# PMD_PROJECT.net
KiCad netlist of a schematic drawn in EasyEDA
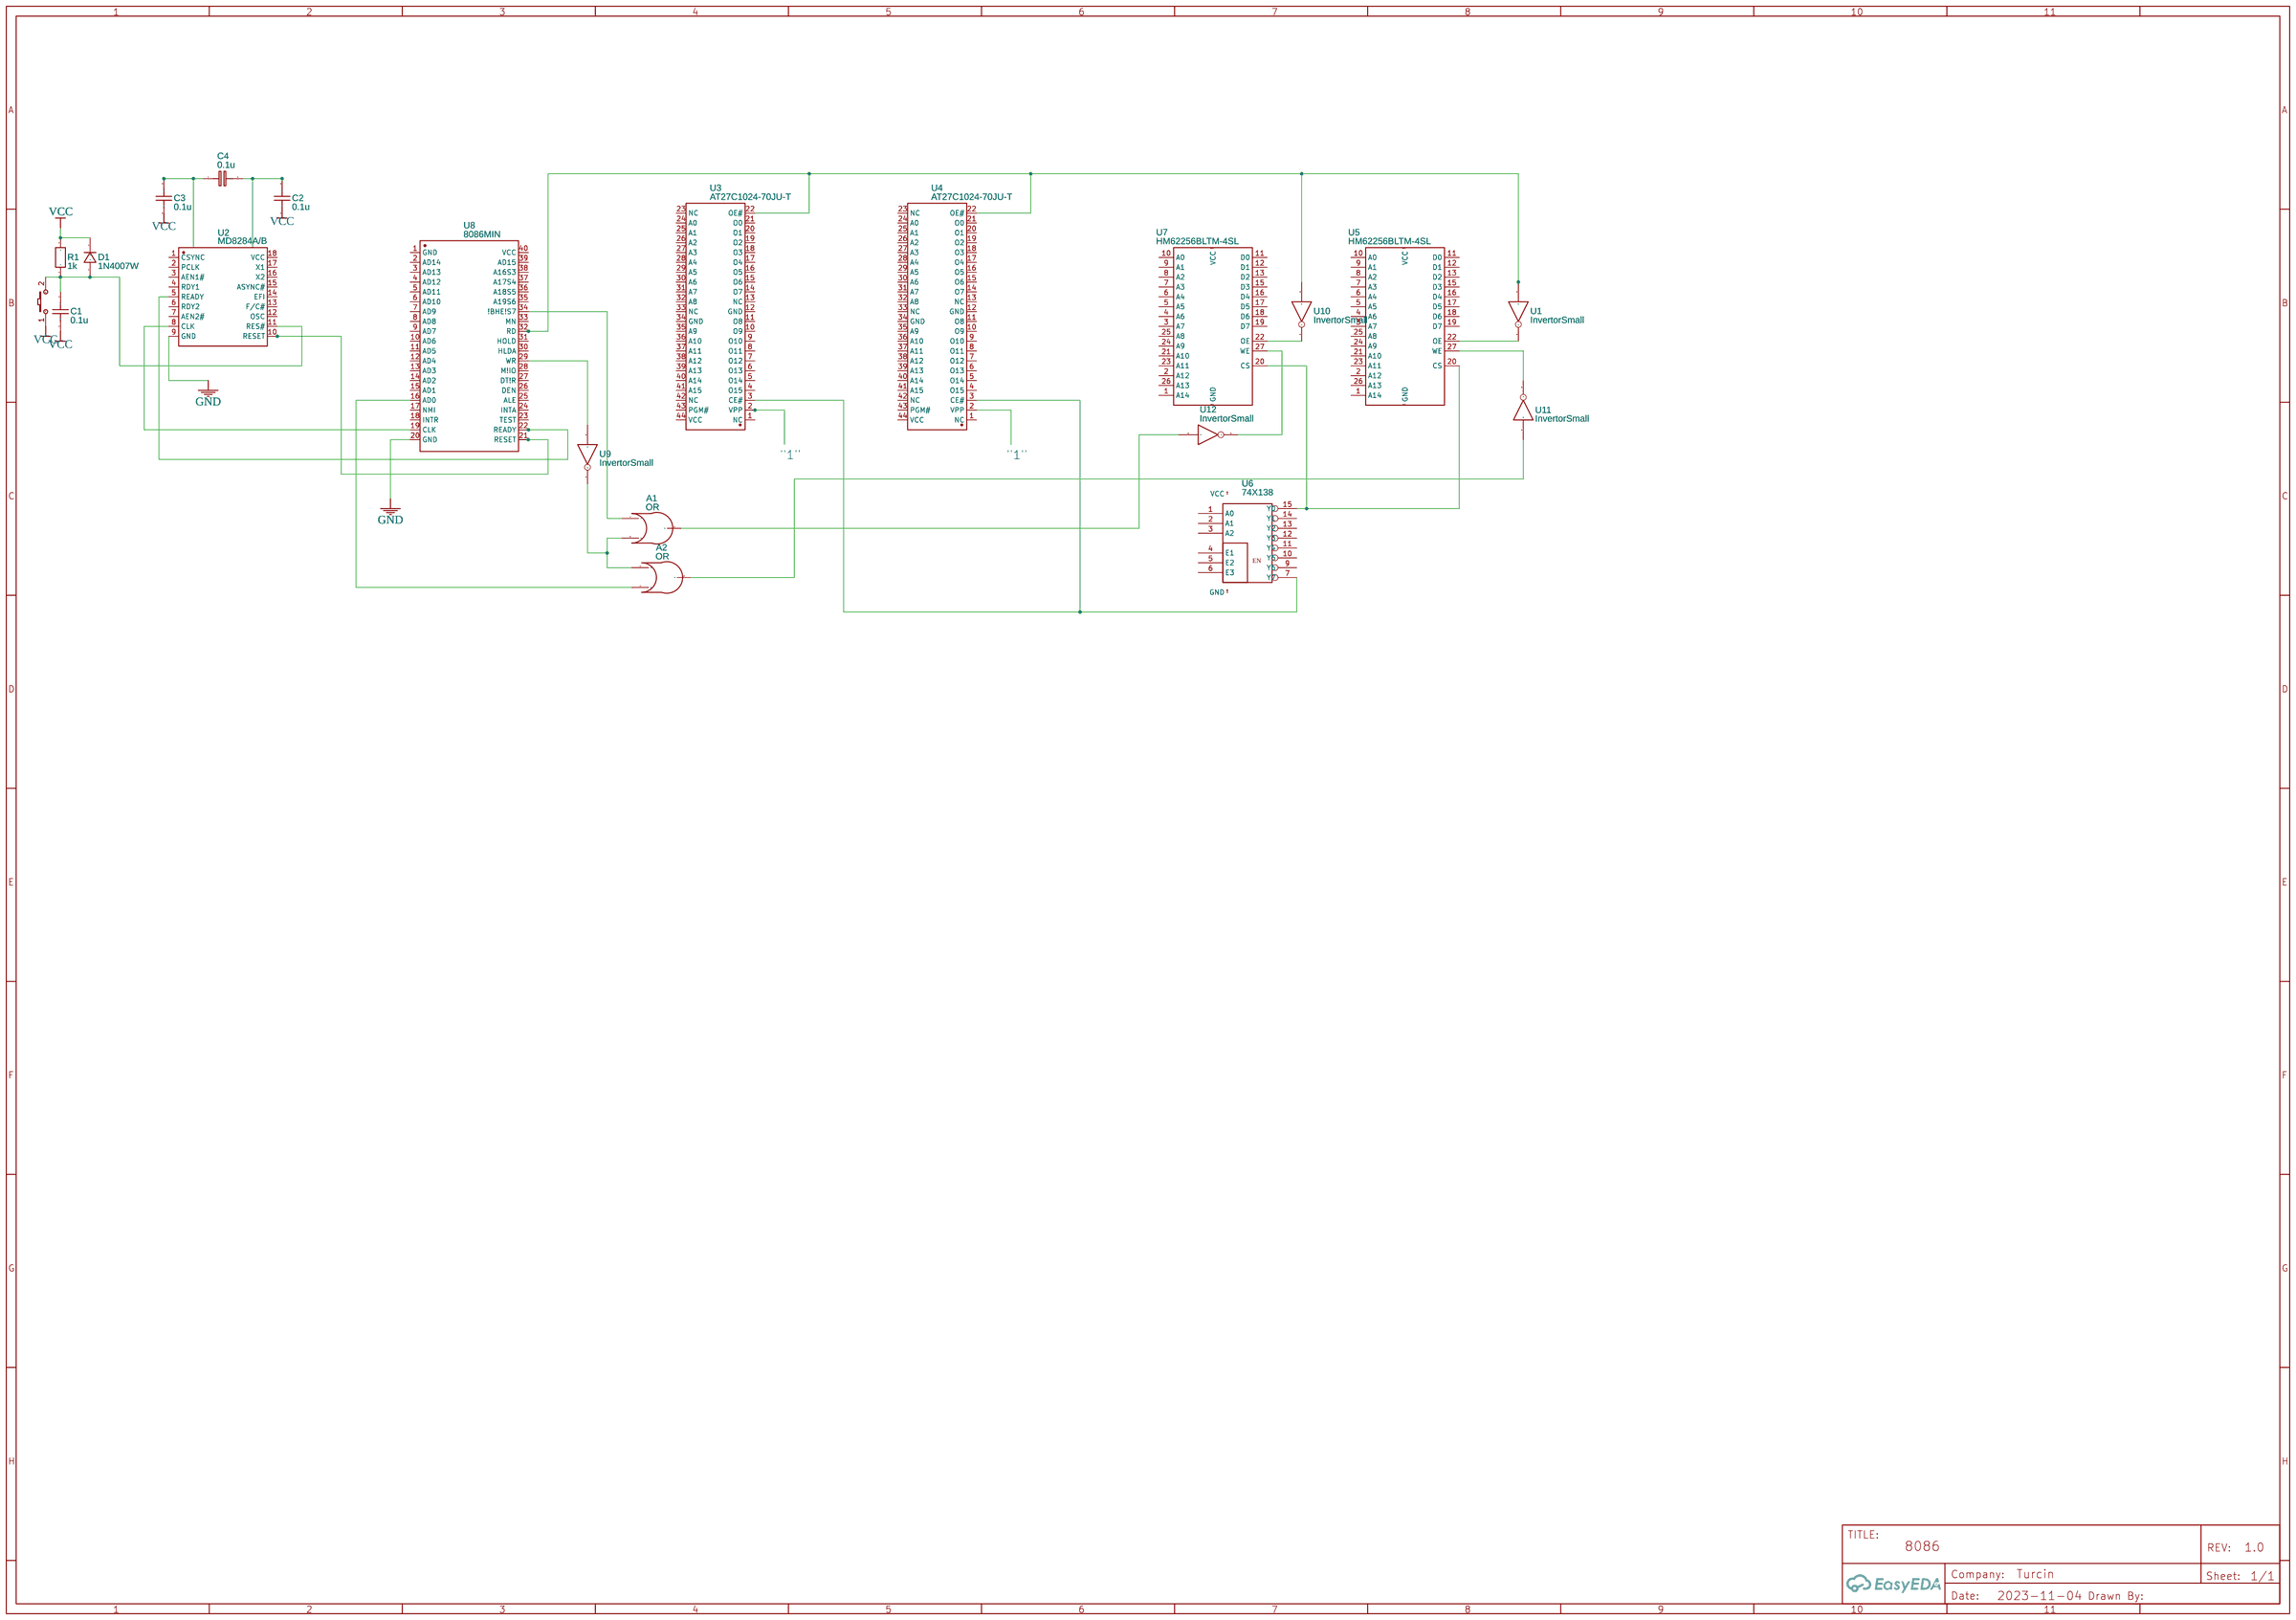
[diagram p0: schematic sheet]

(export (version "E")
  (design (tool "Eeschema 10.0.6"))
  (components
    (comp (ref "A1") (value "OR") (libsource (lib "") (part "OR")))
    (comp (ref "A2") (value "OR") (libsource (lib "") (part "OR")))
    (comp (ref "C1") (value "0.1u") (libsource (lib "") (part "C_0603_US")))
    (comp (ref "C2") (value "0.1u") (libsource (lib "") (part "C_0603_US")))
    (comp (ref "C3") (value "0.1u") (libsource (lib "") (part "C_0603_US")))
    (comp (ref "C4") (value "0.1u") (libsource (lib "") (part "C_0603_EU")))
    (comp (ref "D1")
      (value "1N4007W")
      (fields (field (name "Manufacturer") "BLUE ROCKET"))
      (libsource (lib "") (part "1N4007W"))
    )
    (comp (ref "KEY1")
      (value "K2-3.6×6.1_SMD")
      (fields (field (name "Manufacturer Part") "K2-1107ST-A4SW-06"))
      (libsource (lib "") (part "K2-3.6×6.1_SMD"))
    )
    (comp (ref "R1") (value "1k") (libsource (lib "") (part "R_0603_EU")))
    (comp (ref "U1") (value "InvertorSmall") (libsource (lib "") (part "LOGIC_1")))
    (comp (ref "U2")
      (value "MD8284A/B")
      (fields (field (name "Manufacturer") "罗彻斯特"))
      (libsource (lib "") (part "MD8284A/B"))
    )
    (comp (ref "U3")
      (value "AT27C1024-70JU-T")
      (fields (field (name "Manufacturer") "MICROCHIP(美国微芯)"))
      (libsource (lib "") (part "AT27C1024-70JU-T"))
    )
    (comp (ref "U4")
      (value "AT27C1024-70JU-T")
      (fields (field (name "Manufacturer") "MICROCHIP(美国微芯)"))
      (libsource (lib "") (part "AT27C1024-70JU-T"))
    )
    (comp (ref "U5") (value "HM62256BLTM-4SL") (libsource (lib "") (part "HM62256BLTM-4SL")))
    (comp (ref "U6") (value "74X138") (libsource (lib "") (part "74X138")))
    (comp (ref "U7") (value "HM62256BLTM-4SL") (libsource (lib "") (part "HM62256BLTM-4SL")))
    (comp (ref "U8") (value "8086MIN") (libsource (lib "") (part "8086MIN")))
    (comp (ref "U9") (value "InvertorSmall") (libsource (lib "") (part "LOGIC_1")))
    (comp (ref "U10") (value "InvertorSmall") (libsource (lib "") (part "LOGIC_1")))
    (comp (ref "U11") (value "InvertorSmall") (libsource (lib "") (part "LOGIC_2")))
    (comp (ref "U12") (value "InvertorSmall") (libsource (lib "") (part "LOGIC")))
  )
  (nets
    (net (code "1") (name "GND") (class "Default")
      (node (ref "U2") (pin "9") (pinfunction "GND_9") (pintype "unspecified"))
      (node (ref "U8") (pin "20") (pinfunction "GND_20") (pintype "unspecified"))
    )
    (net (code "2") (name "Net-(C2-Pad2)") (class "Default")
      (node (ref "C2") (pin "2") (pinfunction "2_2") (pintype "unspecified"))
      (node (ref "C4") (pin "2") (pinfunction "2_2") (pintype "unspecified"))
    )
    (net (code "3") (name "Net-(C3-Pad2)") (class "Default")
      (node (ref "C3") (pin "2") (pinfunction "2_2") (pintype "unspecified"))
      (node (ref "C4") (pin "1") (pinfunction "1_1") (pintype "unspecified"))
    )
    (net (code "4") (name "Net-(U1-1)") (class "Default")
      (node (ref "U1") (pin "8") (pinfunction "1_8") (pintype "unspecified"))
      (node (ref "U5") (pin "22") (pinfunction "OE_22") (pintype "input"))
    )
    (net (code "5") (name "Net-(U1-2)") (class "Default")
      (node (ref "U1") (pin "9") (pinfunction "2_9") (pintype "unspecified"))
      (node (ref "U10") (pin "9") (pinfunction "2_9") (pintype "unspecified"))
      (node (ref "U3") (pin "22") (pinfunction "OE#_22") (pintype "unspecified"))
      (node (ref "U4") (pin "22") (pinfunction "OE#_22") (pintype "unspecified"))
      (node (ref "U8") (pin "32") (pinfunction "RD_32") (pintype "unspecified"))
    )
    (net (code "6") (name "Net-(U2-CLK)") (class "Default")
      (node (ref "U2") (pin "8") (pinfunction "CLK_8") (pintype "unspecified"))
      (node (ref "U8") (pin "19") (pinfunction "CLK_19") (pintype "unspecified"))
    )
    (net (code "7") (name "Net-(U2-READY)") (class "Default")
      (node (ref "U2") (pin "5") (pinfunction "READY_5") (pintype "unspecified"))
      (node (ref "U8") (pin "22") (pinfunction "READY_22") (pintype "unspecified"))
    )
    (net (code "8") (name "Net-(U2-RES#)") (class "Default")
      (node (ref "C1") (pin "2") (pinfunction "2_2") (pintype "unspecified"))
      (node (ref "D1") (pin "2") (pinfunction "2_2") (pintype "unspecified"))
      (node (ref "KEY1") (pin "2") (pinfunction "2_2") (pintype "unspecified"))
      (node (ref "R1") (pin "1") (pinfunction "1_1") (pintype "unspecified"))
      (node (ref "U2") (pin "11") (pinfunction "RES#_11") (pintype "unspecified"))
    )
    (net (code "9") (name "Net-(U2-RESET)") (class "Default")
      (node (ref "U2") (pin "10") (pinfunction "RESET_10") (pintype "unspecified"))
      (node (ref "U8") (pin "21") (pinfunction "RESET_21") (pintype "unspecified"))
    )
    (net (code "10") (name "Net-(U3-CE#)") (class "Default")
      (node (ref "U3") (pin "3") (pinfunction "CE#_3") (pintype "unspecified"))
      (node (ref "U4") (pin "3") (pinfunction "CE#_3") (pintype "unspecified"))
      (node (ref "U6") (pin "7") (pinfunction "Y7_7") (pintype "output"))
    )
    (net (code "11") (name "Net-(U5-CS)") (class "Default")
      (node (ref "U5") (pin "20") (pinfunction "CS_20") (pintype "input"))
      (node (ref "U6") (pin "15") (pinfunction "Y0_15") (pintype "output"))
      (node (ref "U7") (pin "20") (pinfunction "CS_20") (pintype "input"))
    )
    (net (code "12") (name "Net-(U8-!BHE!S7)") (class "Default")
      (node (ref "A1") (pin "1") (pinfunction "1_1") (pintype "unspecified"))
      (node (ref "U8") (pin "34") (pinfunction "!BHE!S7_34") (pintype "unspecified"))
    )
    (net (code "13") (name "Net-(U8-AD0)") (class "Default")
      (node (ref "A2") (pin "2") (pinfunction "2_2") (pintype "unspecified"))
      (node (ref "U8") (pin "16") (pinfunction "AD0_16") (pintype "unspecified"))
    )
    (net (code "14") (name "Net-(U8-WR)") (class "Default")
      (node (ref "U8") (pin "29") (pinfunction "WR_29") (pintype "unspecified"))
      (node (ref "U9") (pin "9") (pinfunction "2_9") (pintype "unspecified"))
    )
    (net (code "15") (name "Net-(U9-1)") (class "Default")
      (node (ref "A1") (pin "2") (pinfunction "2_2") (pintype "unspecified"))
      (node (ref "A2") (pin "1") (pinfunction "1_1") (pintype "unspecified"))
      (node (ref "U9") (pin "8") (pinfunction "1_8") (pintype "unspecified"))
    )
    (net (code "16") (name "Net-(U10-1)") (class "Default")
      (node (ref "U10") (pin "8") (pinfunction "1_8") (pintype "unspecified"))
      (node (ref "U7") (pin "22") (pinfunction "OE_22") (pintype "input"))
    )
    (net (code "17") (name "Net-(U11-1)") (class "Default")
      (node (ref "U11") (pin "8") (pinfunction "1_8") (pintype "unspecified"))
      (node (ref "U5") (pin "27") (pinfunction "WE_27") (pintype "input"))
    )
    (net (code "18") (name "Net-(U11-2)") (class "Default")
      (node (ref "A2") (pin "3") (pinfunction "3_3") (pintype "unspecified"))
      (node (ref "U11") (pin "9") (pinfunction "2_9") (pintype "unspecified"))
    )
    (net (code "19") (name "Net-(U12-1)") (class "Default")
      (node (ref "U12") (pin "8") (pinfunction "1_8") (pintype "unspecified"))
      (node (ref "U7") (pin "27") (pinfunction "WE_27") (pintype "input"))
    )
    (net (code "20") (name "Net-(U12-2)") (class "Default")
      (node (ref "A1") (pin "3") (pinfunction "3_3") (pintype "unspecified"))
      (node (ref "U12") (pin "9") (pinfunction "2_9") (pintype "unspecified"))
    )
    (net (code "21") (name "VCC") (class "Default")
      (node (ref "C1") (pin "1") (pinfunction "1_1") (pintype "unspecified"))
      (node (ref "D1") (pin "1") (pinfunction "1_1") (pintype "unspecified"))
      (node (ref "KEY1") (pin "1") (pinfunction "1_1") (pintype "unspecified"))
      (node (ref "R1") (pin "2") (pinfunction "2_2") (pintype "unspecified"))
    )
    (net (code "22") (name "unconnected-(C2-Pad1)") (class "Default")
      (node (ref "C2") (pin "1") (pinfunction "1_1") (pintype "unspecified"))
    )
    (net (code "23") (name "unconnected-(C3-Pad1)") (class "Default")
      (node (ref "C3") (pin "1") (pinfunction "1_1") (pintype "unspecified"))
    )
    (net (code "24") (name "unconnected-(U2-AEN1#-Pad3)") (class "Default")
      (node (ref "U2") (pin "3") (pinfunction "AEN1#_3") (pintype "unspecified"))
    )
    (net (code "25") (name "unconnected-(U2-AEN2#-Pad7)") (class "Default")
      (node (ref "U2") (pin "7") (pinfunction "AEN2#_7") (pintype "unspecified"))
    )
    (net (code "26") (name "unconnected-(U2-ASYNC#-Pad15)") (class "Default")
      (node (ref "U2") (pin "15") (pinfunction "ASYNC#_15") (pintype "unspecified"))
    )
    (net (code "27") (name "unconnected-(U2-CSYNC-Pad1)") (class "Default")
      (node (ref "U2") (pin "1") (pinfunction "CSYNC_1") (pintype "unspecified"))
    )
    (net (code "28") (name "unconnected-(U2-EFI-Pad14)") (class "Default")
      (node (ref "U2") (pin "14") (pinfunction "EFI_14") (pintype "unspecified"))
    )
    (net (code "29") (name "unconnected-(U2-F{slash}C#-Pad13)") (class "Default")
      (node (ref "U2") (pin "13") (pinfunction "F/C#_13") (pintype "unspecified"))
    )
    (net (code "30") (name "unconnected-(U2-OSC-Pad12)") (class "Default")
      (node (ref "U2") (pin "12") (pinfunction "OSC_12") (pintype "unspecified"))
    )
    (net (code "31") (name "unconnected-(U2-PCLK-Pad2)") (class "Default")
      (node (ref "U2") (pin "2") (pinfunction "PCLK_2") (pintype "unspecified"))
    )
    (net (code "32") (name "unconnected-(U2-RDY1-Pad4)") (class "Default")
      (node (ref "U2") (pin "4") (pinfunction "RDY1_4") (pintype "unspecified"))
    )
    (net (code "33") (name "unconnected-(U2-RDY2-Pad6)") (class "Default")
      (node (ref "U2") (pin "6") (pinfunction "RDY2_6") (pintype "unspecified"))
    )
    (net (code "34") (name "unconnected-(U2-VCC-Pad18)") (class "Default")
      (node (ref "U2") (pin "18") (pinfunction "VCC_18") (pintype "unspecified"))
    )
    (net (code "35") (name "unconnected-(U2-X1-Pad17)") (class "Default")
      (node (ref "U2") (pin "17") (pinfunction "X1_17") (pintype "unspecified"))
    )
    (net (code "36") (name "unconnected-(U2-X2-Pad16)") (class "Default")
      (node (ref "U2") (pin "16") (pinfunction "X2_16") (pintype "unspecified"))
    )
    (net (code "37") (name "unconnected-(U3-A0-Pad24)") (class "Default")
      (node (ref "U3") (pin "24") (pinfunction "A0_24") (pintype "unspecified"))
    )
    (net (code "38") (name "unconnected-(U3-A1-Pad25)") (class "Default")
      (node (ref "U3") (pin "25") (pinfunction "A1_25") (pintype "unspecified"))
    )
    (net (code "39") (name "unconnected-(U3-A2-Pad26)") (class "Default")
      (node (ref "U3") (pin "26") (pinfunction "A2_26") (pintype "unspecified"))
    )
    (net (code "40") (name "unconnected-(U3-A3-Pad27)") (class "Default")
      (node (ref "U3") (pin "27") (pinfunction "A3_27") (pintype "unspecified"))
    )
    (net (code "41") (name "unconnected-(U3-A4-Pad28)") (class "Default")
      (node (ref "U3") (pin "28") (pinfunction "A4_28") (pintype "unspecified"))
    )
    (net (code "42") (name "unconnected-(U3-A5-Pad29)") (class "Default")
      (node (ref "U3") (pin "29") (pinfunction "A5_29") (pintype "unspecified"))
    )
    (net (code "43") (name "unconnected-(U3-A6-Pad30)") (class "Default")
      (node (ref "U3") (pin "30") (pinfunction "A6_30") (pintype "unspecified"))
    )
    (net (code "44") (name "unconnected-(U3-A7-Pad31)") (class "Default")
      (node (ref "U3") (pin "31") (pinfunction "A7_31") (pintype "unspecified"))
    )
    (net (code "45") (name "unconnected-(U3-A8-Pad32)") (class "Default")
      (node (ref "U3") (pin "32") (pinfunction "A8_32") (pintype "unspecified"))
    )
    (net (code "46") (name "unconnected-(U3-A9-Pad35)") (class "Default")
      (node (ref "U3") (pin "35") (pinfunction "A9_35") (pintype "unspecified"))
    )
    (net (code "47") (name "unconnected-(U3-A10-Pad36)") (class "Default")
      (node (ref "U3") (pin "36") (pinfunction "A10_36") (pintype "unspecified"))
    )
    (net (code "48") (name "unconnected-(U3-A11-Pad37)") (class "Default")
      (node (ref "U3") (pin "37") (pinfunction "A11_37") (pintype "unspecified"))
    )
    (net (code "49") (name "unconnected-(U3-A12-Pad38)") (class "Default")
      (node (ref "U3") (pin "38") (pinfunction "A12_38") (pintype "unspecified"))
    )
    (net (code "50") (name "unconnected-(U3-A13-Pad39)") (class "Default")
      (node (ref "U3") (pin "39") (pinfunction "A13_39") (pintype "unspecified"))
    )
    (net (code "51") (name "unconnected-(U3-A14-Pad40)") (class "Default")
      (node (ref "U3") (pin "40") (pinfunction "A14_40") (pintype "unspecified"))
    )
    (net (code "52") (name "unconnected-(U3-A15-Pad41)") (class "Default")
      (node (ref "U3") (pin "41") (pinfunction "A15_41") (pintype "unspecified"))
    )
    (net (code "53") (name "unconnected-(U3-GND-Pad12)") (class "Default")
      (node (ref "U3") (pin "12") (pinfunction "GND_12") (pintype "unspecified"))
    )
    (net (code "54") (name "unconnected-(U3-GND-Pad34)") (class "Default")
      (node (ref "U3") (pin "34") (pinfunction "GND_34") (pintype "unspecified"))
    )
    (net (code "55") (name "unconnected-(U3-NC-Pad1)") (class "Default")
      (node (ref "U3") (pin "1") (pinfunction "NC_1") (pintype "unspecified"))
    )
    (net (code "56") (name "unconnected-(U3-NC-Pad13)") (class "Default")
      (node (ref "U3") (pin "13") (pinfunction "NC_13") (pintype "unspecified"))
    )
    (net (code "57") (name "unconnected-(U3-NC-Pad23)") (class "Default")
      (node (ref "U3") (pin "23") (pinfunction "NC_23") (pintype "unspecified"))
    )
    (net (code "58") (name "unconnected-(U3-NC-Pad33)") (class "Default")
      (node (ref "U3") (pin "33") (pinfunction "NC_33") (pintype "unspecified"))
    )
    (net (code "59") (name "unconnected-(U3-NC-Pad42)") (class "Default")
      (node (ref "U3") (pin "42") (pinfunction "NC_42") (pintype "unspecified"))
    )
    (net (code "60") (name "unconnected-(U3-O0-Pad21)") (class "Default")
      (node (ref "U3") (pin "21") (pinfunction "O0_21") (pintype "unspecified"))
    )
    (net (code "61") (name "unconnected-(U3-O1-Pad20)") (class "Default")
      (node (ref "U3") (pin "20") (pinfunction "O1_20") (pintype "unspecified"))
    )
    (net (code "62") (name "unconnected-(U3-O2-Pad19)") (class "Default")
      (node (ref "U3") (pin "19") (pinfunction "O2_19") (pintype "unspecified"))
    )
    (net (code "63") (name "unconnected-(U3-O3-Pad18)") (class "Default")
      (node (ref "U3") (pin "18") (pinfunction "O3_18") (pintype "unspecified"))
    )
    (net (code "64") (name "unconnected-(U3-O4-Pad17)") (class "Default")
      (node (ref "U3") (pin "17") (pinfunction "O4_17") (pintype "unspecified"))
    )
    (net (code "65") (name "unconnected-(U3-O5-Pad16)") (class "Default")
      (node (ref "U3") (pin "16") (pinfunction "O5_16") (pintype "unspecified"))
    )
    (net (code "66") (name "unconnected-(U3-O6-Pad15)") (class "Default")
      (node (ref "U3") (pin "15") (pinfunction "O6_15") (pintype "unspecified"))
    )
    (net (code "67") (name "unconnected-(U3-O7-Pad14)") (class "Default")
      (node (ref "U3") (pin "14") (pinfunction "O7_14") (pintype "unspecified"))
    )
    (net (code "68") (name "unconnected-(U3-O8-Pad11)") (class "Default")
      (node (ref "U3") (pin "11") (pinfunction "O8_11") (pintype "unspecified"))
    )
    (net (code "69") (name "unconnected-(U3-O9-Pad10)") (class "Default")
      (node (ref "U3") (pin "10") (pinfunction "O9_10") (pintype "unspecified"))
    )
    (net (code "70") (name "unconnected-(U3-O10-Pad9)") (class "Default")
      (node (ref "U3") (pin "9") (pinfunction "O10_9") (pintype "unspecified"))
    )
    (net (code "71") (name "unconnected-(U3-O11-Pad8)") (class "Default")
      (node (ref "U3") (pin "8") (pinfunction "O11_8") (pintype "unspecified"))
    )
    (net (code "72") (name "unconnected-(U3-O12-Pad7)") (class "Default")
      (node (ref "U3") (pin "7") (pinfunction "O12_7") (pintype "unspecified"))
    )
    (net (code "73") (name "unconnected-(U3-O13-Pad6)") (class "Default")
      (node (ref "U3") (pin "6") (pinfunction "O13_6") (pintype "unspecified"))
    )
    (net (code "74") (name "unconnected-(U3-O14-Pad5)") (class "Default")
      (node (ref "U3") (pin "5") (pinfunction "O14_5") (pintype "unspecified"))
    )
    (net (code "75") (name "unconnected-(U3-O15-Pad4)") (class "Default")
      (node (ref "U3") (pin "4") (pinfunction "O15_4") (pintype "unspecified"))
    )
    (net (code "76") (name "unconnected-(U3-PGM#-Pad43)") (class "Default")
      (node (ref "U3") (pin "43") (pinfunction "PGM#_43") (pintype "unspecified"))
    )
    (net (code "77") (name "unconnected-(U3-VCC-Pad44)") (class "Default")
      (node (ref "U3") (pin "44") (pinfunction "VCC_44") (pintype "unspecified"))
    )
    (net (code "78") (name "unconnected-(U3-VPP-Pad2)") (class "Default")
      (node (ref "U3") (pin "2") (pinfunction "VPP_2") (pintype "unspecified"))
    )
    (net (code "79") (name "unconnected-(U4-A0-Pad24)") (class "Default")
      (node (ref "U4") (pin "24") (pinfunction "A0_24") (pintype "unspecified"))
    )
    (net (code "80") (name "unconnected-(U4-A1-Pad25)") (class "Default")
      (node (ref "U4") (pin "25") (pinfunction "A1_25") (pintype "unspecified"))
    )
    (net (code "81") (name "unconnected-(U4-A2-Pad26)") (class "Default")
      (node (ref "U4") (pin "26") (pinfunction "A2_26") (pintype "unspecified"))
    )
    (net (code "82") (name "unconnected-(U4-A3-Pad27)") (class "Default")
      (node (ref "U4") (pin "27") (pinfunction "A3_27") (pintype "unspecified"))
    )
    (net (code "83") (name "unconnected-(U4-A4-Pad28)") (class "Default")
      (node (ref "U4") (pin "28") (pinfunction "A4_28") (pintype "unspecified"))
    )
    (net (code "84") (name "unconnected-(U4-A5-Pad29)") (class "Default")
      (node (ref "U4") (pin "29") (pinfunction "A5_29") (pintype "unspecified"))
    )
    (net (code "85") (name "unconnected-(U4-A6-Pad30)") (class "Default")
      (node (ref "U4") (pin "30") (pinfunction "A6_30") (pintype "unspecified"))
    )
    (net (code "86") (name "unconnected-(U4-A7-Pad31)") (class "Default")
      (node (ref "U4") (pin "31") (pinfunction "A7_31") (pintype "unspecified"))
    )
    (net (code "87") (name "unconnected-(U4-A8-Pad32)") (class "Default")
      (node (ref "U4") (pin "32") (pinfunction "A8_32") (pintype "unspecified"))
    )
    (net (code "88") (name "unconnected-(U4-A9-Pad35)") (class "Default")
      (node (ref "U4") (pin "35") (pinfunction "A9_35") (pintype "unspecified"))
    )
    (net (code "89") (name "unconnected-(U4-A10-Pad36)") (class "Default")
      (node (ref "U4") (pin "36") (pinfunction "A10_36") (pintype "unspecified"))
    )
    (net (code "90") (name "unconnected-(U4-A11-Pad37)") (class "Default")
      (node (ref "U4") (pin "37") (pinfunction "A11_37") (pintype "unspecified"))
    )
    (net (code "91") (name "unconnected-(U4-A12-Pad38)") (class "Default")
      (node (ref "U4") (pin "38") (pinfunction "A12_38") (pintype "unspecified"))
    )
    (net (code "92") (name "unconnected-(U4-A13-Pad39)") (class "Default")
      (node (ref "U4") (pin "39") (pinfunction "A13_39") (pintype "unspecified"))
    )
    (net (code "93") (name "unconnected-(U4-A14-Pad40)") (class "Default")
      (node (ref "U4") (pin "40") (pinfunction "A14_40") (pintype "unspecified"))
    )
    (net (code "94") (name "unconnected-(U4-A15-Pad41)") (class "Default")
      (node (ref "U4") (pin "41") (pinfunction "A15_41") (pintype "unspecified"))
    )
    (net (code "95") (name "unconnected-(U4-GND-Pad12)") (class "Default")
      (node (ref "U4") (pin "12") (pinfunction "GND_12") (pintype "unspecified"))
    )
    (net (code "96") (name "unconnected-(U4-GND-Pad34)") (class "Default")
      (node (ref "U4") (pin "34") (pinfunction "GND_34") (pintype "unspecified"))
    )
    (net (code "97") (name "unconnected-(U4-NC-Pad1)") (class "Default")
      (node (ref "U4") (pin "1") (pinfunction "NC_1") (pintype "unspecified"))
    )
    (net (code "98") (name "unconnected-(U4-NC-Pad13)") (class "Default")
      (node (ref "U4") (pin "13") (pinfunction "NC_13") (pintype "unspecified"))
    )
    (net (code "99") (name "unconnected-(U4-NC-Pad23)") (class "Default")
      (node (ref "U4") (pin "23") (pinfunction "NC_23") (pintype "unspecified"))
    )
    (net (code "100") (name "unconnected-(U4-NC-Pad33)") (class "Default")
      (node (ref "U4") (pin "33") (pinfunction "NC_33") (pintype "unspecified"))
    )
    (net (code "101") (name "unconnected-(U4-NC-Pad42)") (class "Default")
      (node (ref "U4") (pin "42") (pinfunction "NC_42") (pintype "unspecified"))
    )
    (net (code "102") (name "unconnected-(U4-O0-Pad21)") (class "Default")
      (node (ref "U4") (pin "21") (pinfunction "O0_21") (pintype "unspecified"))
    )
    (net (code "103") (name "unconnected-(U4-O1-Pad20)") (class "Default")
      (node (ref "U4") (pin "20") (pinfunction "O1_20") (pintype "unspecified"))
    )
    (net (code "104") (name "unconnected-(U4-O2-Pad19)") (class "Default")
      (node (ref "U4") (pin "19") (pinfunction "O2_19") (pintype "unspecified"))
    )
    (net (code "105") (name "unconnected-(U4-O3-Pad18)") (class "Default")
      (node (ref "U4") (pin "18") (pinfunction "O3_18") (pintype "unspecified"))
    )
    (net (code "106") (name "unconnected-(U4-O4-Pad17)") (class "Default")
      (node (ref "U4") (pin "17") (pinfunction "O4_17") (pintype "unspecified"))
    )
    (net (code "107") (name "unconnected-(U4-O5-Pad16)") (class "Default")
      (node (ref "U4") (pin "16") (pinfunction "O5_16") (pintype "unspecified"))
    )
    (net (code "108") (name "unconnected-(U4-O6-Pad15)") (class "Default")
      (node (ref "U4") (pin "15") (pinfunction "O6_15") (pintype "unspecified"))
    )
    (net (code "109") (name "unconnected-(U4-O7-Pad14)") (class "Default")
      (node (ref "U4") (pin "14") (pinfunction "O7_14") (pintype "unspecified"))
    )
    (net (code "110") (name "unconnected-(U4-O8-Pad11)") (class "Default")
      (node (ref "U4") (pin "11") (pinfunction "O8_11") (pintype "unspecified"))
    )
    (net (code "111") (name "unconnected-(U4-O9-Pad10)") (class "Default")
      (node (ref "U4") (pin "10") (pinfunction "O9_10") (pintype "unspecified"))
    )
    (net (code "112") (name "unconnected-(U4-O10-Pad9)") (class "Default")
      (node (ref "U4") (pin "9") (pinfunction "O10_9") (pintype "unspecified"))
    )
    (net (code "113") (name "unconnected-(U4-O11-Pad8)") (class "Default")
      (node (ref "U4") (pin "8") (pinfunction "O11_8") (pintype "unspecified"))
    )
    (net (code "114") (name "unconnected-(U4-O12-Pad7)") (class "Default")
      (node (ref "U4") (pin "7") (pinfunction "O12_7") (pintype "unspecified"))
    )
    (net (code "115") (name "unconnected-(U4-O13-Pad6)") (class "Default")
      (node (ref "U4") (pin "6") (pinfunction "O13_6") (pintype "unspecified"))
    )
    (net (code "116") (name "unconnected-(U4-O14-Pad5)") (class "Default")
      (node (ref "U4") (pin "5") (pinfunction "O14_5") (pintype "unspecified"))
    )
    (net (code "117") (name "unconnected-(U4-O15-Pad4)") (class "Default")
      (node (ref "U4") (pin "4") (pinfunction "O15_4") (pintype "unspecified"))
    )
    (net (code "118") (name "unconnected-(U4-PGM#-Pad43)") (class "Default")
      (node (ref "U4") (pin "43") (pinfunction "PGM#_43") (pintype "unspecified"))
    )
    (net (code "119") (name "unconnected-(U4-VCC-Pad44)") (class "Default")
      (node (ref "U4") (pin "44") (pinfunction "VCC_44") (pintype "unspecified"))
    )
    (net (code "120") (name "unconnected-(U4-VPP-Pad2)") (class "Default")
      (node (ref "U4") (pin "2") (pinfunction "VPP_2") (pintype "unspecified"))
    )
    (net (code "121") (name "unconnected-(U5-A0-Pad10)") (class "Default")
      (node (ref "U5") (pin "10") (pinfunction "A0_10") (pintype "input"))
    )
    (net (code "122") (name "unconnected-(U5-A1-Pad9)") (class "Default")
      (node (ref "U5") (pin "9") (pinfunction "A1_9") (pintype "input"))
    )
    (net (code "123") (name "unconnected-(U5-A2-Pad8)") (class "Default")
      (node (ref "U5") (pin "8") (pinfunction "A2_8") (pintype "input"))
    )
    (net (code "124") (name "unconnected-(U5-A3-Pad7)") (class "Default")
      (node (ref "U5") (pin "7") (pinfunction "A3_7") (pintype "input"))
    )
    (net (code "125") (name "unconnected-(U5-A4-Pad6)") (class "Default")
      (node (ref "U5") (pin "6") (pinfunction "A4_6") (pintype "input"))
    )
    (net (code "126") (name "unconnected-(U5-A5-Pad5)") (class "Default")
      (node (ref "U5") (pin "5") (pinfunction "A5_5") (pintype "input"))
    )
    (net (code "127") (name "unconnected-(U5-A6-Pad4)") (class "Default")
      (node (ref "U5") (pin "4") (pinfunction "A6_4") (pintype "input"))
    )
    (net (code "128") (name "unconnected-(U5-A7-Pad3)") (class "Default")
      (node (ref "U5") (pin "3") (pinfunction "A7_3") (pintype "input"))
    )
    (net (code "129") (name "unconnected-(U5-A8-Pad25)") (class "Default")
      (node (ref "U5") (pin "25") (pinfunction "A8_25") (pintype "input"))
    )
    (net (code "130") (name "unconnected-(U5-A9-Pad24)") (class "Default")
      (node (ref "U5") (pin "24") (pinfunction "A9_24") (pintype "input"))
    )
    (net (code "131") (name "unconnected-(U5-A10-Pad21)") (class "Default")
      (node (ref "U5") (pin "21") (pinfunction "A10_21") (pintype "input"))
    )
    (net (code "132") (name "unconnected-(U5-A11-Pad23)") (class "Default")
      (node (ref "U5") (pin "23") (pinfunction "A11_23") (pintype "input"))
    )
    (net (code "133") (name "unconnected-(U5-A12-Pad2)") (class "Default")
      (node (ref "U5") (pin "2") (pinfunction "A12_2") (pintype "input"))
    )
    (net (code "134") (name "unconnected-(U5-A13-Pad26)") (class "Default")
      (node (ref "U5") (pin "26") (pinfunction "A13_26") (pintype "input"))
    )
    (net (code "135") (name "unconnected-(U5-A14-Pad1)") (class "Default")
      (node (ref "U5") (pin "1") (pinfunction "A14_1") (pintype "input"))
    )
    (net (code "136") (name "unconnected-(U5-D0-Pad11)") (class "Default")
      (node (ref "U5") (pin "11") (pinfunction "D0_11") (pintype "unspecified"))
    )
    (net (code "137") (name "unconnected-(U5-D1-Pad12)") (class "Default")
      (node (ref "U5") (pin "12") (pinfunction "D1_12") (pintype "unspecified"))
    )
    (net (code "138") (name "unconnected-(U5-D2-Pad13)") (class "Default")
      (node (ref "U5") (pin "13") (pinfunction "D2_13") (pintype "unspecified"))
    )
    (net (code "139") (name "unconnected-(U5-D3-Pad15)") (class "Default")
      (node (ref "U5") (pin "15") (pinfunction "D3_15") (pintype "unspecified"))
    )
    (net (code "140") (name "unconnected-(U5-D4-Pad16)") (class "Default")
      (node (ref "U5") (pin "16") (pinfunction "D4_16") (pintype "unspecified"))
    )
    (net (code "141") (name "unconnected-(U5-D5-Pad17)") (class "Default")
      (node (ref "U5") (pin "17") (pinfunction "D5_17") (pintype "unspecified"))
    )
    (net (code "142") (name "unconnected-(U5-D6-Pad18)") (class "Default")
      (node (ref "U5") (pin "18") (pinfunction "D6_18") (pintype "unspecified"))
    )
    (net (code "143") (name "unconnected-(U5-D7-Pad19)") (class "Default")
      (node (ref "U5") (pin "19") (pinfunction "D7_19") (pintype "unspecified"))
    )
    (net (code "144") (name "unconnected-(U5-GND-Pad14)") (class "Default")
      (node (ref "U5") (pin "14") (pinfunction "GND_14") (pintype "passive"))
    )
    (net (code "145") (name "unconnected-(U5-VCC-Pad28)") (class "Default")
      (node (ref "U5") (pin "28") (pinfunction "VCC_28") (pintype "passive"))
    )
    (net (code "146") (name "unconnected-(U6-A0-Pad1)") (class "Default")
      (node (ref "U6") (pin "1") (pinfunction "A0_1") (pintype "input"))
    )
    (net (code "147") (name "unconnected-(U6-A1-Pad2)") (class "Default")
      (node (ref "U6") (pin "2") (pinfunction "A1_2") (pintype "input"))
    )
    (net (code "148") (name "unconnected-(U6-A2-Pad3)") (class "Default")
      (node (ref "U6") (pin "3") (pinfunction "A2_3") (pintype "input"))
    )
    (net (code "149") (name "unconnected-(U6-E1-Pad4)") (class "Default")
      (node (ref "U6") (pin "4") (pinfunction "E1_4") (pintype "input"))
    )
    (net (code "150") (name "unconnected-(U6-E2-Pad5)") (class "Default")
      (node (ref "U6") (pin "5") (pinfunction "E2_5") (pintype "input"))
    )
    (net (code "151") (name "unconnected-(U6-E3-Pad6)") (class "Default")
      (node (ref "U6") (pin "6") (pinfunction "E3_6") (pintype "input"))
    )
    (net (code "152") (name "unconnected-(U6-GND-Pad8)") (class "Default")
      (node (ref "U6") (pin "8") (pinfunction "GND_8") (pintype "passive"))
    )
    (net (code "153") (name "unconnected-(U6-VCC-Pad16)") (class "Default")
      (node (ref "U6") (pin "16") (pinfunction "VCC_16") (pintype "passive"))
    )
    (net (code "154") (name "unconnected-(U6-Y1-Pad14)") (class "Default")
      (node (ref "U6") (pin "14") (pinfunction "Y1_14") (pintype "output"))
    )
    (net (code "155") (name "unconnected-(U6-Y2-Pad13)") (class "Default")
      (node (ref "U6") (pin "13") (pinfunction "Y2_13") (pintype "output"))
    )
    (net (code "156") (name "unconnected-(U6-Y3-Pad12)") (class "Default")
      (node (ref "U6") (pin "12") (pinfunction "Y3_12") (pintype "output"))
    )
    (net (code "157") (name "unconnected-(U6-Y4-Pad11)") (class "Default")
      (node (ref "U6") (pin "11") (pinfunction "Y4_11") (pintype "output"))
    )
    (net (code "158") (name "unconnected-(U6-Y5-Pad10)") (class "Default")
      (node (ref "U6") (pin "10") (pinfunction "Y5_10") (pintype "output"))
    )
    (net (code "159") (name "unconnected-(U6-Y6-Pad9)") (class "Default")
      (node (ref "U6") (pin "9") (pinfunction "Y6_9") (pintype "output"))
    )
    (net (code "160") (name "unconnected-(U7-A0-Pad10)") (class "Default")
      (node (ref "U7") (pin "10") (pinfunction "A0_10") (pintype "input"))
    )
    (net (code "161") (name "unconnected-(U7-A1-Pad9)") (class "Default")
      (node (ref "U7") (pin "9") (pinfunction "A1_9") (pintype "input"))
    )
    (net (code "162") (name "unconnected-(U7-A2-Pad8)") (class "Default")
      (node (ref "U7") (pin "8") (pinfunction "A2_8") (pintype "input"))
    )
    (net (code "163") (name "unconnected-(U7-A3-Pad7)") (class "Default")
      (node (ref "U7") (pin "7") (pinfunction "A3_7") (pintype "input"))
    )
    (net (code "164") (name "unconnected-(U7-A4-Pad6)") (class "Default")
      (node (ref "U7") (pin "6") (pinfunction "A4_6") (pintype "input"))
    )
    (net (code "165") (name "unconnected-(U7-A5-Pad5)") (class "Default")
      (node (ref "U7") (pin "5") (pinfunction "A5_5") (pintype "input"))
    )
    (net (code "166") (name "unconnected-(U7-A6-Pad4)") (class "Default")
      (node (ref "U7") (pin "4") (pinfunction "A6_4") (pintype "input"))
    )
    (net (code "167") (name "unconnected-(U7-A7-Pad3)") (class "Default")
      (node (ref "U7") (pin "3") (pinfunction "A7_3") (pintype "input"))
    )
    (net (code "168") (name "unconnected-(U7-A8-Pad25)") (class "Default")
      (node (ref "U7") (pin "25") (pinfunction "A8_25") (pintype "input"))
    )
    (net (code "169") (name "unconnected-(U7-A9-Pad24)") (class "Default")
      (node (ref "U7") (pin "24") (pinfunction "A9_24") (pintype "input"))
    )
    (net (code "170") (name "unconnected-(U7-A10-Pad21)") (class "Default")
      (node (ref "U7") (pin "21") (pinfunction "A10_21") (pintype "input"))
    )
    (net (code "171") (name "unconnected-(U7-A11-Pad23)") (class "Default")
      (node (ref "U7") (pin "23") (pinfunction "A11_23") (pintype "input"))
    )
    (net (code "172") (name "unconnected-(U7-A12-Pad2)") (class "Default")
      (node (ref "U7") (pin "2") (pinfunction "A12_2") (pintype "input"))
    )
    (net (code "173") (name "unconnected-(U7-A13-Pad26)") (class "Default")
      (node (ref "U7") (pin "26") (pinfunction "A13_26") (pintype "input"))
    )
    (net (code "174") (name "unconnected-(U7-A14-Pad1)") (class "Default")
      (node (ref "U7") (pin "1") (pinfunction "A14_1") (pintype "input"))
    )
    (net (code "175") (name "unconnected-(U7-D0-Pad11)") (class "Default")
      (node (ref "U7") (pin "11") (pinfunction "D0_11") (pintype "unspecified"))
    )
    (net (code "176") (name "unconnected-(U7-D1-Pad12)") (class "Default")
      (node (ref "U7") (pin "12") (pinfunction "D1_12") (pintype "unspecified"))
    )
    (net (code "177") (name "unconnected-(U7-D2-Pad13)") (class "Default")
      (node (ref "U7") (pin "13") (pinfunction "D2_13") (pintype "unspecified"))
    )
    (net (code "178") (name "unconnected-(U7-D3-Pad15)") (class "Default")
      (node (ref "U7") (pin "15") (pinfunction "D3_15") (pintype "unspecified"))
    )
    (net (code "179") (name "unconnected-(U7-D4-Pad16)") (class "Default")
      (node (ref "U7") (pin "16") (pinfunction "D4_16") (pintype "unspecified"))
    )
    (net (code "180") (name "unconnected-(U7-D5-Pad17)") (class "Default")
      (node (ref "U7") (pin "17") (pinfunction "D5_17") (pintype "unspecified"))
    )
    (net (code "181") (name "unconnected-(U7-D6-Pad18)") (class "Default")
      (node (ref "U7") (pin "18") (pinfunction "D6_18") (pintype "unspecified"))
    )
    (net (code "182") (name "unconnected-(U7-D7-Pad19)") (class "Default")
      (node (ref "U7") (pin "19") (pinfunction "D7_19") (pintype "unspecified"))
    )
    (net (code "183") (name "unconnected-(U7-GND-Pad14)") (class "Default")
      (node (ref "U7") (pin "14") (pinfunction "GND_14") (pintype "passive"))
    )
    (net (code "184") (name "unconnected-(U7-VCC-Pad28)") (class "Default")
      (node (ref "U7") (pin "28") (pinfunction "VCC_28") (pintype "passive"))
    )
    (net (code "185") (name "unconnected-(U8-A16S3-Pad38)") (class "Default")
      (node (ref "U8") (pin "38") (pinfunction "A16S3_38") (pintype "unspecified"))
    )
    (net (code "186") (name "unconnected-(U8-A17S4-Pad37)") (class "Default")
      (node (ref "U8") (pin "37") (pinfunction "A17S4_37") (pintype "unspecified"))
    )
    (net (code "187") (name "unconnected-(U8-A18S5-Pad36)") (class "Default")
      (node (ref "U8") (pin "36") (pinfunction "A18S5_36") (pintype "unspecified"))
    )
    (net (code "188") (name "unconnected-(U8-A19S6-Pad35)") (class "Default")
      (node (ref "U8") (pin "35") (pinfunction "A19S6_35") (pintype "unspecified"))
    )
    (net (code "189") (name "unconnected-(U8-AD1-Pad15)") (class "Default")
      (node (ref "U8") (pin "15") (pinfunction "AD1_15") (pintype "unspecified"))
    )
    (net (code "190") (name "unconnected-(U8-AD2-Pad14)") (class "Default")
      (node (ref "U8") (pin "14") (pinfunction "AD2_14") (pintype "unspecified"))
    )
    (net (code "191") (name "unconnected-(U8-AD3-Pad13)") (class "Default")
      (node (ref "U8") (pin "13") (pinfunction "AD3_13") (pintype "unspecified"))
    )
    (net (code "192") (name "unconnected-(U8-AD4-Pad12)") (class "Default")
      (node (ref "U8") (pin "12") (pinfunction "AD4_12") (pintype "unspecified"))
    )
    (net (code "193") (name "unconnected-(U8-AD5-Pad11)") (class "Default")
      (node (ref "U8") (pin "11") (pinfunction "AD5_11") (pintype "unspecified"))
    )
    (net (code "194") (name "unconnected-(U8-AD6-Pad10)") (class "Default")
      (node (ref "U8") (pin "10") (pinfunction "AD6_10") (pintype "unspecified"))
    )
    (net (code "195") (name "unconnected-(U8-AD7-Pad9)") (class "Default")
      (node (ref "U8") (pin "9") (pinfunction "AD7_9") (pintype "unspecified"))
    )
    (net (code "196") (name "unconnected-(U8-AD8-Pad8)") (class "Default")
      (node (ref "U8") (pin "8") (pinfunction "AD8_8") (pintype "unspecified"))
    )
    (net (code "197") (name "unconnected-(U8-AD9-Pad7)") (class "Default")
      (node (ref "U8") (pin "7") (pinfunction "AD9_7") (pintype "unspecified"))
    )
    (net (code "198") (name "unconnected-(U8-AD10-Pad6)") (class "Default")
      (node (ref "U8") (pin "6") (pinfunction "AD10_6") (pintype "unspecified"))
    )
    (net (code "199") (name "unconnected-(U8-AD11-Pad5)") (class "Default")
      (node (ref "U8") (pin "5") (pinfunction "AD11_5") (pintype "unspecified"))
    )
    (net (code "200") (name "unconnected-(U8-AD12-Pad4)") (class "Default")
      (node (ref "U8") (pin "4") (pinfunction "AD12_4") (pintype "unspecified"))
    )
    (net (code "201") (name "unconnected-(U8-AD13-Pad3)") (class "Default")
      (node (ref "U8") (pin "3") (pinfunction "AD13_3") (pintype "unspecified"))
    )
    (net (code "202") (name "unconnected-(U8-AD14-Pad2)") (class "Default")
      (node (ref "U8") (pin "2") (pinfunction "AD14_2") (pintype "unspecified"))
    )
    (net (code "203") (name "unconnected-(U8-AD15-Pad39)") (class "Default")
      (node (ref "U8") (pin "39") (pinfunction "AD15_39") (pintype "unspecified"))
    )
    (net (code "204") (name "unconnected-(U8-ALE-Pad25)") (class "Default")
      (node (ref "U8") (pin "25") (pinfunction "ALE_25") (pintype "unspecified"))
    )
    (net (code "205") (name "unconnected-(U8-DEN-Pad26)") (class "Default")
      (node (ref "U8") (pin "26") (pinfunction "DEN_26") (pintype "unspecified"))
    )
    (net (code "206") (name "unconnected-(U8-DT!R-Pad27)") (class "Default")
      (node (ref "U8") (pin "27") (pinfunction "DT!R_27") (pintype "unspecified"))
    )
    (net (code "207") (name "unconnected-(U8-GND-Pad1)") (class "Default")
      (node (ref "U8") (pin "1") (pinfunction "GND_1") (pintype "unspecified"))
    )
    (net (code "208") (name "unconnected-(U8-HLDA-Pad30)") (class "Default")
      (node (ref "U8") (pin "30") (pinfunction "HLDA_30") (pintype "unspecified"))
    )
    (net (code "209") (name "unconnected-(U8-HOLD-Pad31)") (class "Default")
      (node (ref "U8") (pin "31") (pinfunction "HOLD_31") (pintype "unspecified"))
    )
    (net (code "210") (name "unconnected-(U8-INTA-Pad24)") (class "Default")
      (node (ref "U8") (pin "24") (pinfunction "INTA_24") (pintype "unspecified"))
    )
    (net (code "211") (name "unconnected-(U8-INTR-Pad18)") (class "Default")
      (node (ref "U8") (pin "18") (pinfunction "INTR_18") (pintype "unspecified"))
    )
    (net (code "212") (name "unconnected-(U8-M!IO-Pad28)") (class "Default")
      (node (ref "U8") (pin "28") (pinfunction "M!IO_28") (pintype "unspecified"))
    )
    (net (code "213") (name "unconnected-(U8-MN-Pad33)") (class "Default")
      (node (ref "U8") (pin "33") (pinfunction "MN_33") (pintype "unspecified"))
    )
    (net (code "214") (name "unconnected-(U8-NMI-Pad17)") (class "Default")
      (node (ref "U8") (pin "17") (pinfunction "NMI_17") (pintype "unspecified"))
    )
    (net (code "215") (name "unconnected-(U8-TEST-Pad23)") (class "Default")
      (node (ref "U8") (pin "23") (pinfunction "TEST_23") (pintype "unspecified"))
    )
    (net (code "216") (name "unconnected-(U8-VCC-Pad40)") (class "Default")
      (node (ref "U8") (pin "40") (pinfunction "VCC_40") (pintype "unspecified"))
    )
  )
)
